# Split_propu2026.net
KiCad netlist of a schematic drawn in Altium Designer
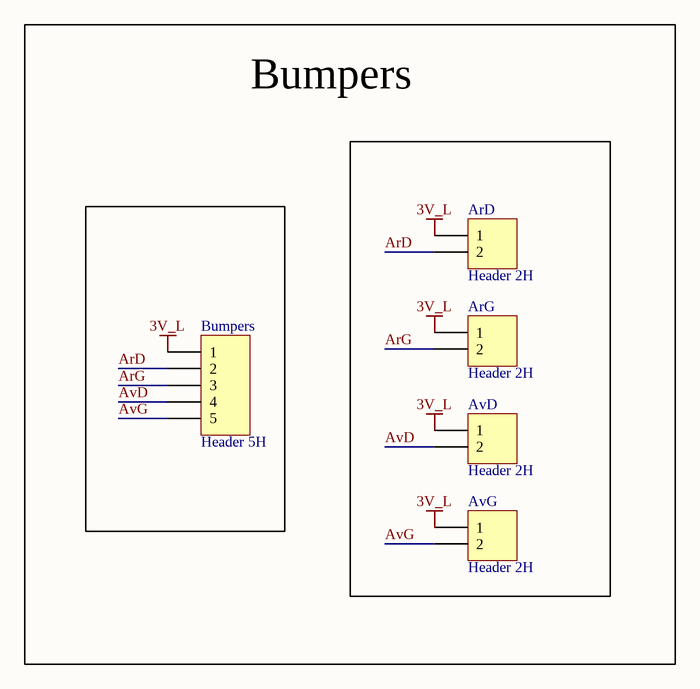
[diagram p0: Split_propu2026.SchDoc]

(export (version "E")
  (design (tool "Eeschema 10.0.6"))
  (components
    (comp (ref "ArD")
      (value "Header 2H")
      (footprint "S2B-XH-A")
      (description "Header, 2-Pin, Right Angle")
      (fields (field (name "PUBLISHER") "Altium Limited"))
      (libsource (lib "Miscellaneous Connectors") (part "Header 2H"))
    )
    (comp (ref "ArG")
      (value "Header 2H")
      (footprint "S2B-XH-A")
      (description "Header, 2-Pin, Right Angle")
      (fields (field (name "PUBLISHER") "Altium Limited"))
      (libsource (lib "Miscellaneous Connectors") (part "Header 2H"))
    )
    (comp (ref "AvD")
      (value "Header 2H")
      (footprint "S2B-XH-A")
      (description "Header, 2-Pin, Right Angle")
      (fields (field (name "PUBLISHER") "Altium Limited"))
      (libsource (lib "Miscellaneous Connectors") (part "Header 2H"))
    )
    (comp (ref "AvG")
      (value "Header 2H")
      (footprint "S2B-XH-A")
      (description "Header, 2-Pin, Right Angle")
      (fields (field (name "PUBLISHER") "Altium Limited"))
      (libsource (lib "Miscellaneous Connectors") (part "Header 2H"))
    )
    (comp (ref "Bumpers")
      (value "Header 5H")
      (footprint "S5B-XH-A")
      (description "Header, 5-Pin, Right Angle")
      (fields (field (name "PUBLISHER") "Altium Limited"))
      (libsource (lib "Miscellaneous Connectors") (part "Header 5H"))
    )
  )
  (nets
    (net (code "1") (name "/ArD") (class "Default")
      (node (ref "ArD") (pin "2") (pinfunction "2_2") (pintype "passive"))
      (node (ref "Bumpers") (pin "2") (pinfunction "2_2") (pintype "passive"))
    )
    (net (code "2") (name "/ArG") (class "Default")
      (node (ref "ArG") (pin "2") (pinfunction "2_2") (pintype "passive"))
      (node (ref "Bumpers") (pin "3") (pinfunction "3_3") (pintype "passive"))
    )
    (net (code "3") (name "/AvD") (class "Default")
      (node (ref "AvD") (pin "2") (pinfunction "2_2") (pintype "passive"))
      (node (ref "Bumpers") (pin "4") (pinfunction "4_4") (pintype "passive"))
    )
    (net (code "4") (name "/AvG") (class "Default")
      (node (ref "AvG") (pin "2") (pinfunction "2_2") (pintype "passive"))
      (node (ref "Bumpers") (pin "5") (pinfunction "5_5") (pintype "passive"))
    )
    (net (code "5") (name "3V_L") (class "Default")
      (node (ref "ArD") (pin "1") (pinfunction "1_1") (pintype "passive"))
      (node (ref "ArG") (pin "1") (pinfunction "1_1") (pintype "passive"))
      (node (ref "AvD") (pin "1") (pinfunction "1_1") (pintype "passive"))
      (node (ref "AvG") (pin "1") (pinfunction "1_1") (pintype "passive"))
      (node (ref "Bumpers") (pin "1") (pinfunction "1_1") (pintype "passive"))
    )
  )
)
